# ble_car_0_1.net
KiCad netlist of a schematic drawn in EasyEDA
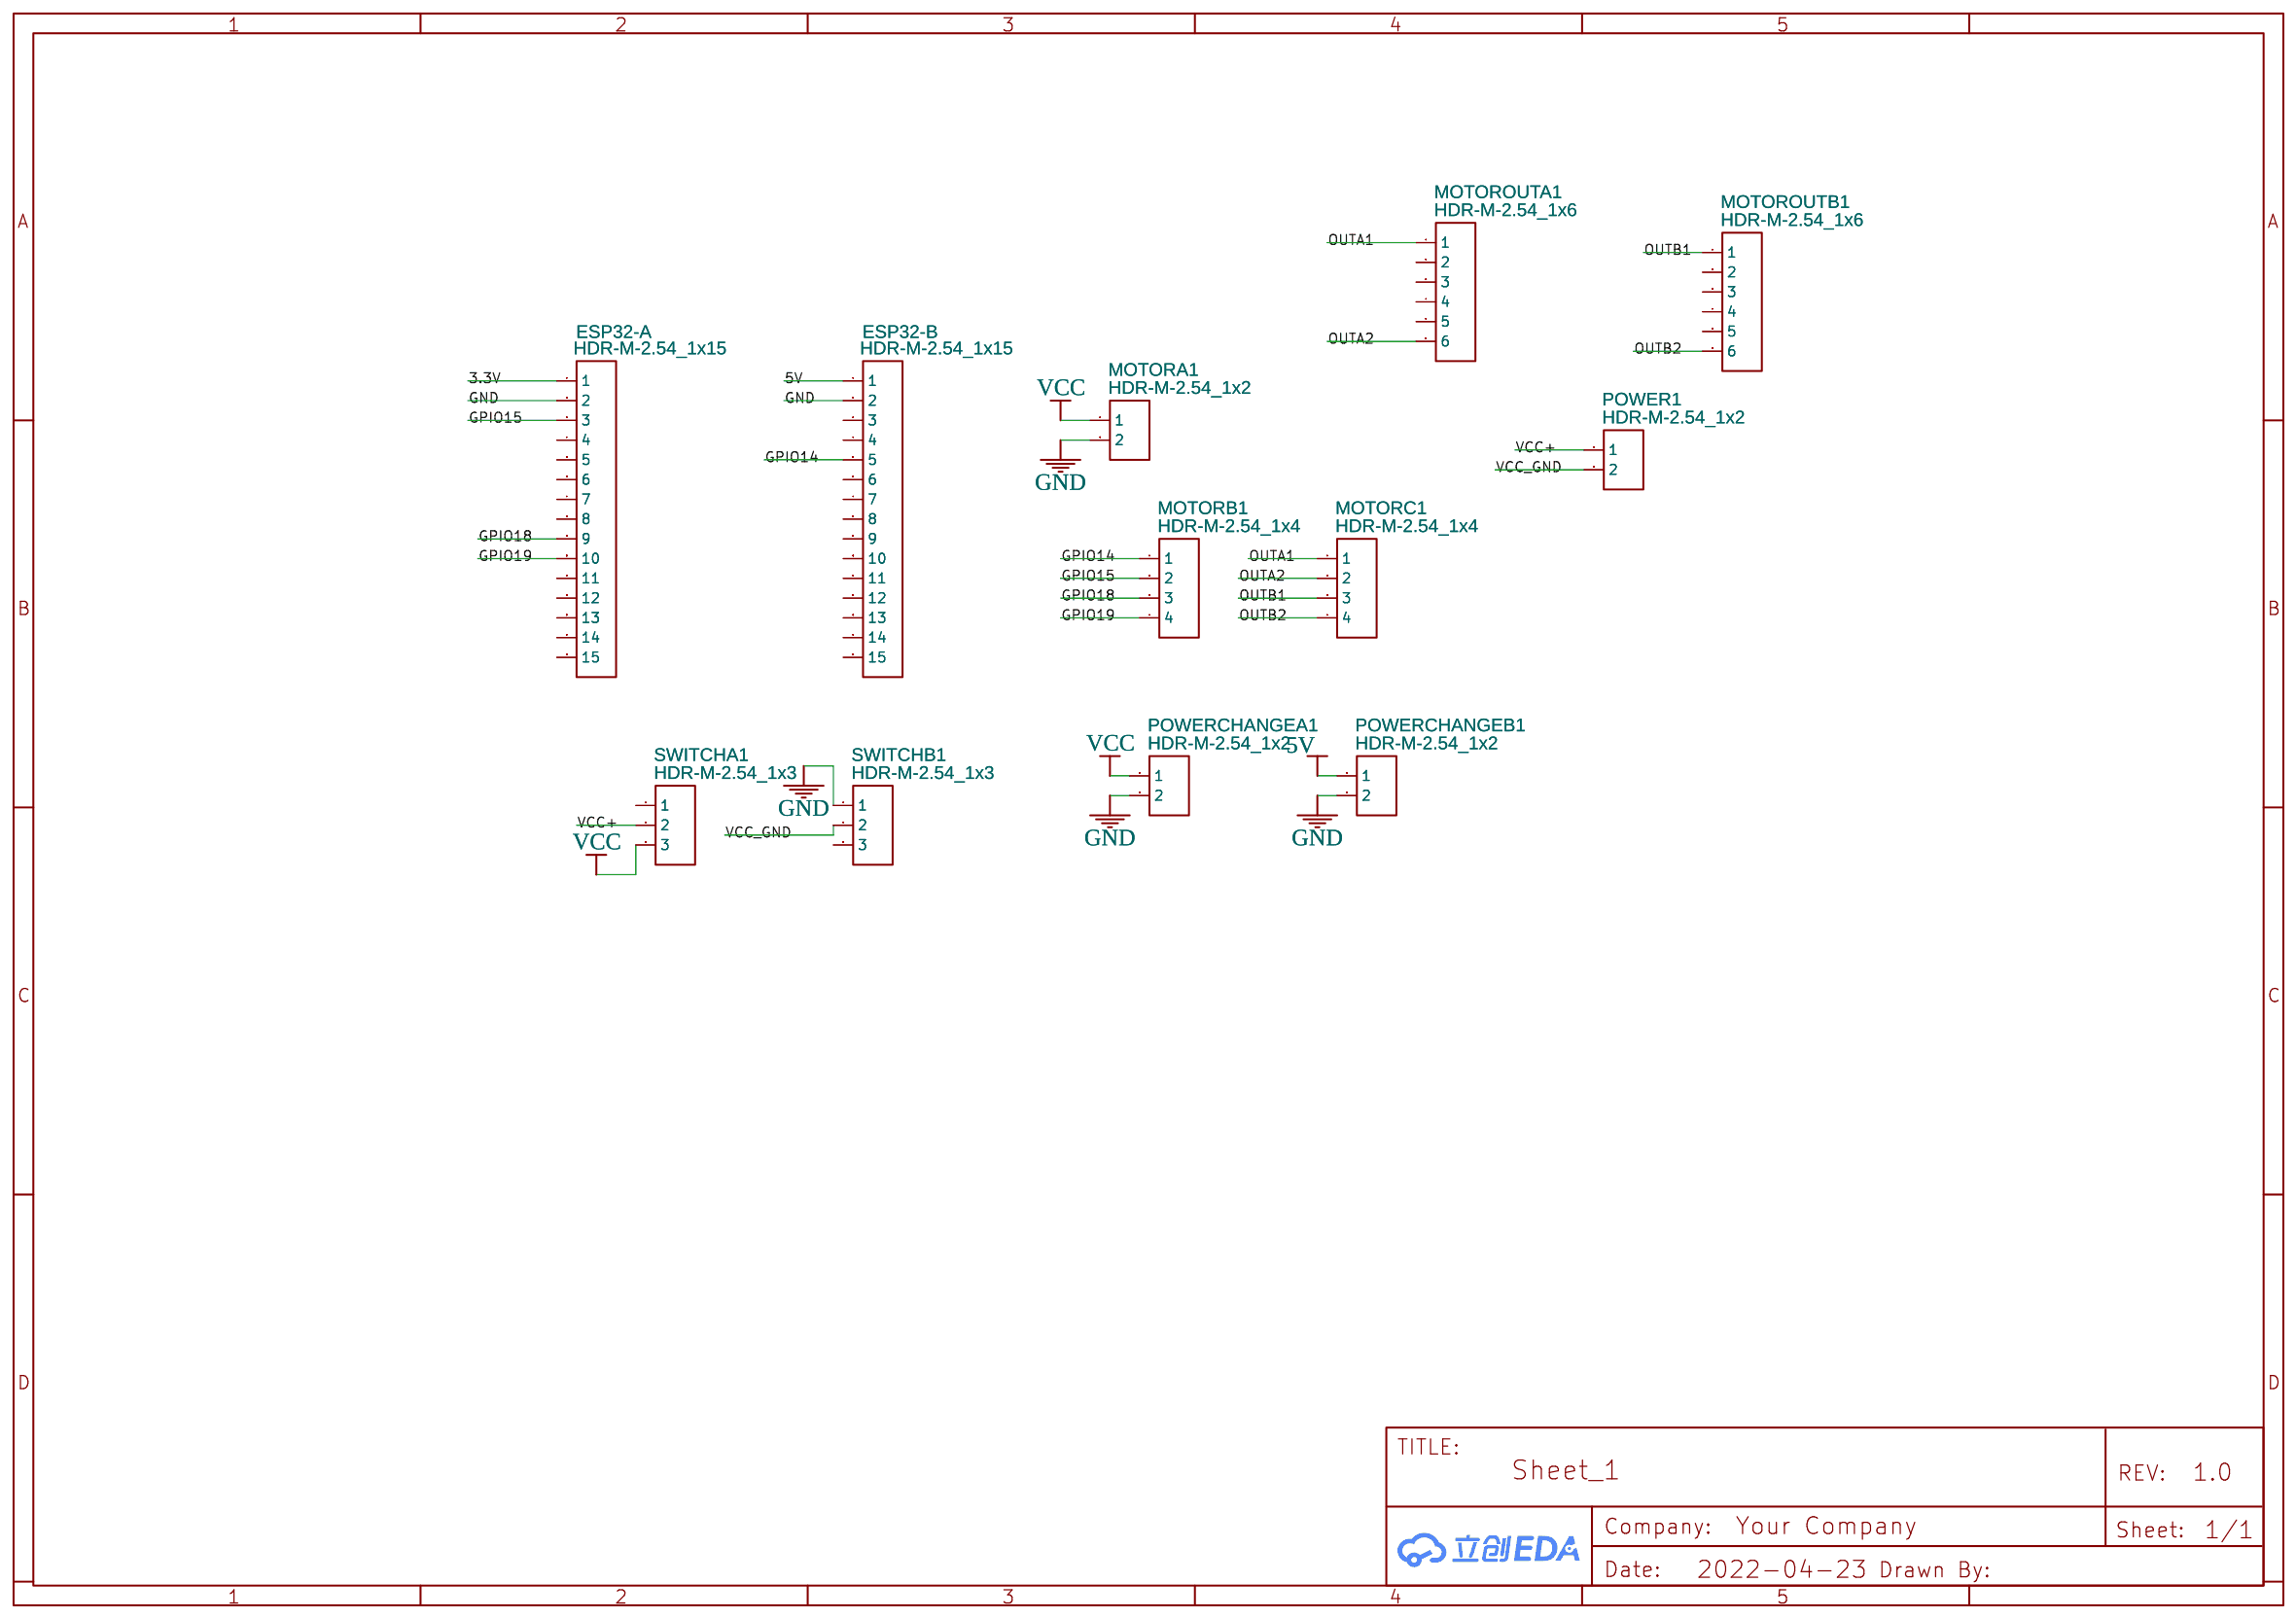
[diagram p0: schematic sheet]

(export (version "E")
  (design (tool "Eeschema 10.0.6"))
  (components
    (comp (ref "ESP32-A")
      (value "HDR-M-2.54_1x15")
      (fields (field (name "BOM_Supplier Part") "C124373"))
      (libsource (lib "") (part "HDR-M-2.54_1x15"))
    )
    (comp (ref "ESP32-B")
      (value "HDR-M-2.54_1x15")
      (fields (field (name "BOM_Supplier Part") "C124373"))
      (libsource (lib "") (part "HDR-M-2.54_1x15_1"))
    )
    (comp (ref "MOTORA1")
      (value "HDR-M-2.54_1x2")
      (fields (field (name "BOM_Supplier Part") "C124375"))
      (libsource (lib "") (part "HDR-M-2.54_1x2_2"))
    )
    (comp (ref "MOTORB1")
      (value "HDR-M-2.54_1x4")
      (fields (field (name "BOM_Supplier Part") "C124378"))
      (libsource (lib "") (part "HDR-M-2.54_1x4"))
    )
    (comp (ref "MOTORC1")
      (value "HDR-M-2.54_1x4")
      (fields (field (name "BOM_Supplier Part") "C124378"))
      (libsource (lib "") (part "HDR-M-2.54_1x4_1"))
    )
    (comp (ref "MOTOROUTA1")
      (value "HDR-M-2.54_1x6")
      (fields (field (name "BOM_Supplier Part") "C190819"))
      (libsource (lib "") (part "HDR-M-2.54_1x6_1"))
    )
    (comp (ref "MOTOROUTB1")
      (value "HDR-M-2.54_1x6")
      (fields (field (name "BOM_Supplier Part") "C190819"))
      (libsource (lib "") (part "HDR-M-2.54_1x6"))
    )
    (comp (ref "POWER1")
      (value "HDR-M-2.54_1x2")
      (fields (field (name "BOM_Supplier Part") "C124375"))
      (libsource (lib "") (part "HDR-M-2.54_1x2_1"))
    )
    (comp (ref "POWERCHANGEA1")
      (value "HDR-M-2.54_1x2")
      (fields (field (name "BOM_Supplier Part") "C124375"))
      (libsource (lib "") (part "HDR-M-2.54_1x2_3"))
    )
    (comp (ref "POWERCHANGEB1")
      (value "HDR-M-2.54_1x2")
      (fields (field (name "BOM_Supplier Part") "C124375"))
      (libsource (lib "") (part "HDR-M-2.54_1x2"))
    )
    (comp (ref "SWITCHA1")
      (value "HDR-M-2.54_1x3")
      (fields (field (name "BOM_Supplier Part") "C180248"))
      (libsource (lib "") (part "HDR-M-2.54_1x3_1"))
    )
    (comp (ref "SWITCHB1")
      (value "HDR-M-2.54_1x3")
      (fields (field (name "BOM_Supplier Part") "C180248"))
      (libsource (lib "") (part "HDR-M-2.54_1x3"))
    )
  )
  (nets
    (net (code "1") (name "/3.3V") (class "Default")
      (node (ref "ESP32-A") (pin "1") (pinfunction "1_1") (pintype "unspecified"))
    )
    (net (code "2") (name "/GPIO14") (class "Default")
      (node (ref "ESP32-B") (pin "5") (pinfunction "5_5") (pintype "unspecified"))
      (node (ref "MOTORB1") (pin "1") (pinfunction "1_1") (pintype "unspecified"))
    )
    (net (code "3") (name "/GPIO15") (class "Default")
      (node (ref "ESP32-A") (pin "3") (pinfunction "3_3") (pintype "unspecified"))
      (node (ref "MOTORB1") (pin "2") (pinfunction "2_2") (pintype "unspecified"))
    )
    (net (code "4") (name "/GPIO18") (class "Default")
      (node (ref "ESP32-A") (pin "9") (pinfunction "9_9") (pintype "unspecified"))
      (node (ref "MOTORB1") (pin "3") (pinfunction "3_3") (pintype "unspecified"))
    )
    (net (code "5") (name "/GPIO19") (class "Default")
      (node (ref "ESP32-A") (pin "10") (pinfunction "10_10") (pintype "unspecified"))
      (node (ref "MOTORB1") (pin "4") (pinfunction "4_4") (pintype "unspecified"))
    )
    (net (code "6") (name "/OUTA1") (class "Default")
      (node (ref "MOTORC1") (pin "1") (pinfunction "1_1") (pintype "unspecified"))
      (node (ref "MOTOROUTA1") (pin "1") (pinfunction "1_1") (pintype "input"))
    )
    (net (code "7") (name "/OUTA2") (class "Default")
      (node (ref "MOTORC1") (pin "2") (pinfunction "2_2") (pintype "unspecified"))
      (node (ref "MOTOROUTA1") (pin "6") (pinfunction "6_6") (pintype "input"))
    )
    (net (code "8") (name "/OUTB1") (class "Default")
      (node (ref "MOTORC1") (pin "3") (pinfunction "3_3") (pintype "unspecified"))
      (node (ref "MOTOROUTB1") (pin "1") (pinfunction "1_1") (pintype "input"))
    )
    (net (code "9") (name "/OUTB2") (class "Default")
      (node (ref "MOTORC1") (pin "4") (pinfunction "4_4") (pintype "unspecified"))
      (node (ref "MOTOROUTB1") (pin "6") (pinfunction "6_6") (pintype "input"))
    )
    (net (code "10") (name "/VCC+") (class "Default")
      (node (ref "POWER1") (pin "1") (pinfunction "1_1") (pintype "unspecified"))
      (node (ref "SWITCHA1") (pin "2") (pinfunction "2_2") (pintype "input"))
    )
    (net (code "11") (name "/VCC_GND") (class "Default")
      (node (ref "POWER1") (pin "2") (pinfunction "2_2") (pintype "unspecified"))
      (node (ref "SWITCHB1") (pin "2") (pinfunction "2_2") (pintype "input"))
    )
    (net (code "12") (name "5V") (class "Default")
      (node (ref "ESP32-B") (pin "1") (pinfunction "1_1") (pintype "unspecified"))
      (node (ref "POWERCHANGEB1") (pin "1") (pinfunction "1_1") (pintype "unspecified"))
    )
    (net (code "13") (name "GND") (class "Default")
      (node (ref "ESP32-A") (pin "2") (pinfunction "2_2") (pintype "unspecified"))
      (node (ref "ESP32-B") (pin "2") (pinfunction "2_2") (pintype "unspecified"))
      (node (ref "MOTORA1") (pin "2") (pinfunction "2_2") (pintype "unspecified"))
      (node (ref "POWERCHANGEA1") (pin "2") (pinfunction "2_2") (pintype "unspecified"))
      (node (ref "POWERCHANGEB1") (pin "2") (pinfunction "2_2") (pintype "unspecified"))
      (node (ref "SWITCHB1") (pin "1") (pinfunction "1_1") (pintype "input"))
    )
    (net (code "14") (name "VCC") (class "Default")
      (node (ref "MOTORA1") (pin "1") (pinfunction "1_1") (pintype "unspecified"))
      (node (ref "POWERCHANGEA1") (pin "1") (pinfunction "1_1") (pintype "unspecified"))
      (node (ref "SWITCHA1") (pin "3") (pinfunction "3_3") (pintype "input"))
    )
    (net (code "15") (name "unconnected-(ESP32-A-Pad4)") (class "Default")
      (node (ref "ESP32-A") (pin "4") (pinfunction "4_4") (pintype "unspecified"))
    )
    (net (code "16") (name "unconnected-(ESP32-A-Pad5)") (class "Default")
      (node (ref "ESP32-A") (pin "5") (pinfunction "5_5") (pintype "unspecified"))
    )
    (net (code "17") (name "unconnected-(ESP32-A-Pad6)") (class "Default")
      (node (ref "ESP32-A") (pin "6") (pinfunction "6_6") (pintype "unspecified"))
    )
    (net (code "18") (name "unconnected-(ESP32-A-Pad7)") (class "Default")
      (node (ref "ESP32-A") (pin "7") (pinfunction "7_7") (pintype "unspecified"))
    )
    (net (code "19") (name "unconnected-(ESP32-A-Pad8)") (class "Default")
      (node (ref "ESP32-A") (pin "8") (pinfunction "8_8") (pintype "unspecified"))
    )
    (net (code "20") (name "unconnected-(ESP32-A-Pad11)") (class "Default")
      (node (ref "ESP32-A") (pin "11") (pinfunction "11_11") (pintype "unspecified"))
    )
    (net (code "21") (name "unconnected-(ESP32-A-Pad12)") (class "Default")
      (node (ref "ESP32-A") (pin "12") (pinfunction "12_12") (pintype "unspecified"))
    )
    (net (code "22") (name "unconnected-(ESP32-A-Pad13)") (class "Default")
      (node (ref "ESP32-A") (pin "13") (pinfunction "13_13") (pintype "unspecified"))
    )
    (net (code "23") (name "unconnected-(ESP32-A-Pad14)") (class "Default")
      (node (ref "ESP32-A") (pin "14") (pinfunction "14_14") (pintype "unspecified"))
    )
    (net (code "24") (name "unconnected-(ESP32-A-Pad15)") (class "Default")
      (node (ref "ESP32-A") (pin "15") (pinfunction "15_15") (pintype "unspecified"))
    )
    (net (code "25") (name "unconnected-(ESP32-B-Pad3)") (class "Default")
      (node (ref "ESP32-B") (pin "3") (pinfunction "3_3") (pintype "unspecified"))
    )
    (net (code "26") (name "unconnected-(ESP32-B-Pad4)") (class "Default")
      (node (ref "ESP32-B") (pin "4") (pinfunction "4_4") (pintype "unspecified"))
    )
    (net (code "27") (name "unconnected-(ESP32-B-Pad6)") (class "Default")
      (node (ref "ESP32-B") (pin "6") (pinfunction "6_6") (pintype "unspecified"))
    )
    (net (code "28") (name "unconnected-(ESP32-B-Pad7)") (class "Default")
      (node (ref "ESP32-B") (pin "7") (pinfunction "7_7") (pintype "unspecified"))
    )
    (net (code "29") (name "unconnected-(ESP32-B-Pad8)") (class "Default")
      (node (ref "ESP32-B") (pin "8") (pinfunction "8_8") (pintype "unspecified"))
    )
    (net (code "30") (name "unconnected-(ESP32-B-Pad9)") (class "Default")
      (node (ref "ESP32-B") (pin "9") (pinfunction "9_9") (pintype "unspecified"))
    )
    (net (code "31") (name "unconnected-(ESP32-B-Pad10)") (class "Default")
      (node (ref "ESP32-B") (pin "10") (pinfunction "10_10") (pintype "unspecified"))
    )
    (net (code "32") (name "unconnected-(ESP32-B-Pad11)") (class "Default")
      (node (ref "ESP32-B") (pin "11") (pinfunction "11_11") (pintype "unspecified"))
    )
    (net (code "33") (name "unconnected-(ESP32-B-Pad12)") (class "Default")
      (node (ref "ESP32-B") (pin "12") (pinfunction "12_12") (pintype "unspecified"))
    )
    (net (code "34") (name "unconnected-(ESP32-B-Pad13)") (class "Default")
      (node (ref "ESP32-B") (pin "13") (pinfunction "13_13") (pintype "unspecified"))
    )
    (net (code "35") (name "unconnected-(ESP32-B-Pad14)") (class "Default")
      (node (ref "ESP32-B") (pin "14") (pinfunction "14_14") (pintype "unspecified"))
    )
    (net (code "36") (name "unconnected-(ESP32-B-Pad15)") (class "Default")
      (node (ref "ESP32-B") (pin "15") (pinfunction "15_15") (pintype "unspecified"))
    )
    (net (code "37") (name "unconnected-(MOTOROUTA1-Pad2)") (class "Default")
      (node (ref "MOTOROUTA1") (pin "2") (pinfunction "2_2") (pintype "input"))
    )
    (net (code "38") (name "unconnected-(MOTOROUTA1-Pad3)") (class "Default")
      (node (ref "MOTOROUTA1") (pin "3") (pinfunction "3_3") (pintype "input"))
    )
    (net (code "39") (name "unconnected-(MOTOROUTA1-Pad4)") (class "Default")
      (node (ref "MOTOROUTA1") (pin "4") (pinfunction "4_4") (pintype "input"))
    )
    (net (code "40") (name "unconnected-(MOTOROUTA1-Pad5)") (class "Default")
      (node (ref "MOTOROUTA1") (pin "5") (pinfunction "5_5") (pintype "input"))
    )
    (net (code "41") (name "unconnected-(MOTOROUTB1-Pad2)") (class "Default")
      (node (ref "MOTOROUTB1") (pin "2") (pinfunction "2_2") (pintype "input"))
    )
    (net (code "42") (name "unconnected-(MOTOROUTB1-Pad3)") (class "Default")
      (node (ref "MOTOROUTB1") (pin "3") (pinfunction "3_3") (pintype "input"))
    )
    (net (code "43") (name "unconnected-(MOTOROUTB1-Pad4)") (class "Default")
      (node (ref "MOTOROUTB1") (pin "4") (pinfunction "4_4") (pintype "input"))
    )
    (net (code "44") (name "unconnected-(MOTOROUTB1-Pad5)") (class "Default")
      (node (ref "MOTOROUTB1") (pin "5") (pinfunction "5_5") (pintype "input"))
    )
    (net (code "45") (name "unconnected-(SWITCHA1-Pad1)") (class "Default")
      (node (ref "SWITCHA1") (pin "1") (pinfunction "1_1") (pintype "input"))
    )
    (net (code "46") (name "unconnected-(SWITCHB1-Pad3)") (class "Default")
      (node (ref "SWITCHB1") (pin "3") (pinfunction "3_3") (pintype "input"))
    )
  )
)
